# source.net
KiCad netlist of a schematic drawn in EasyEDA Pro
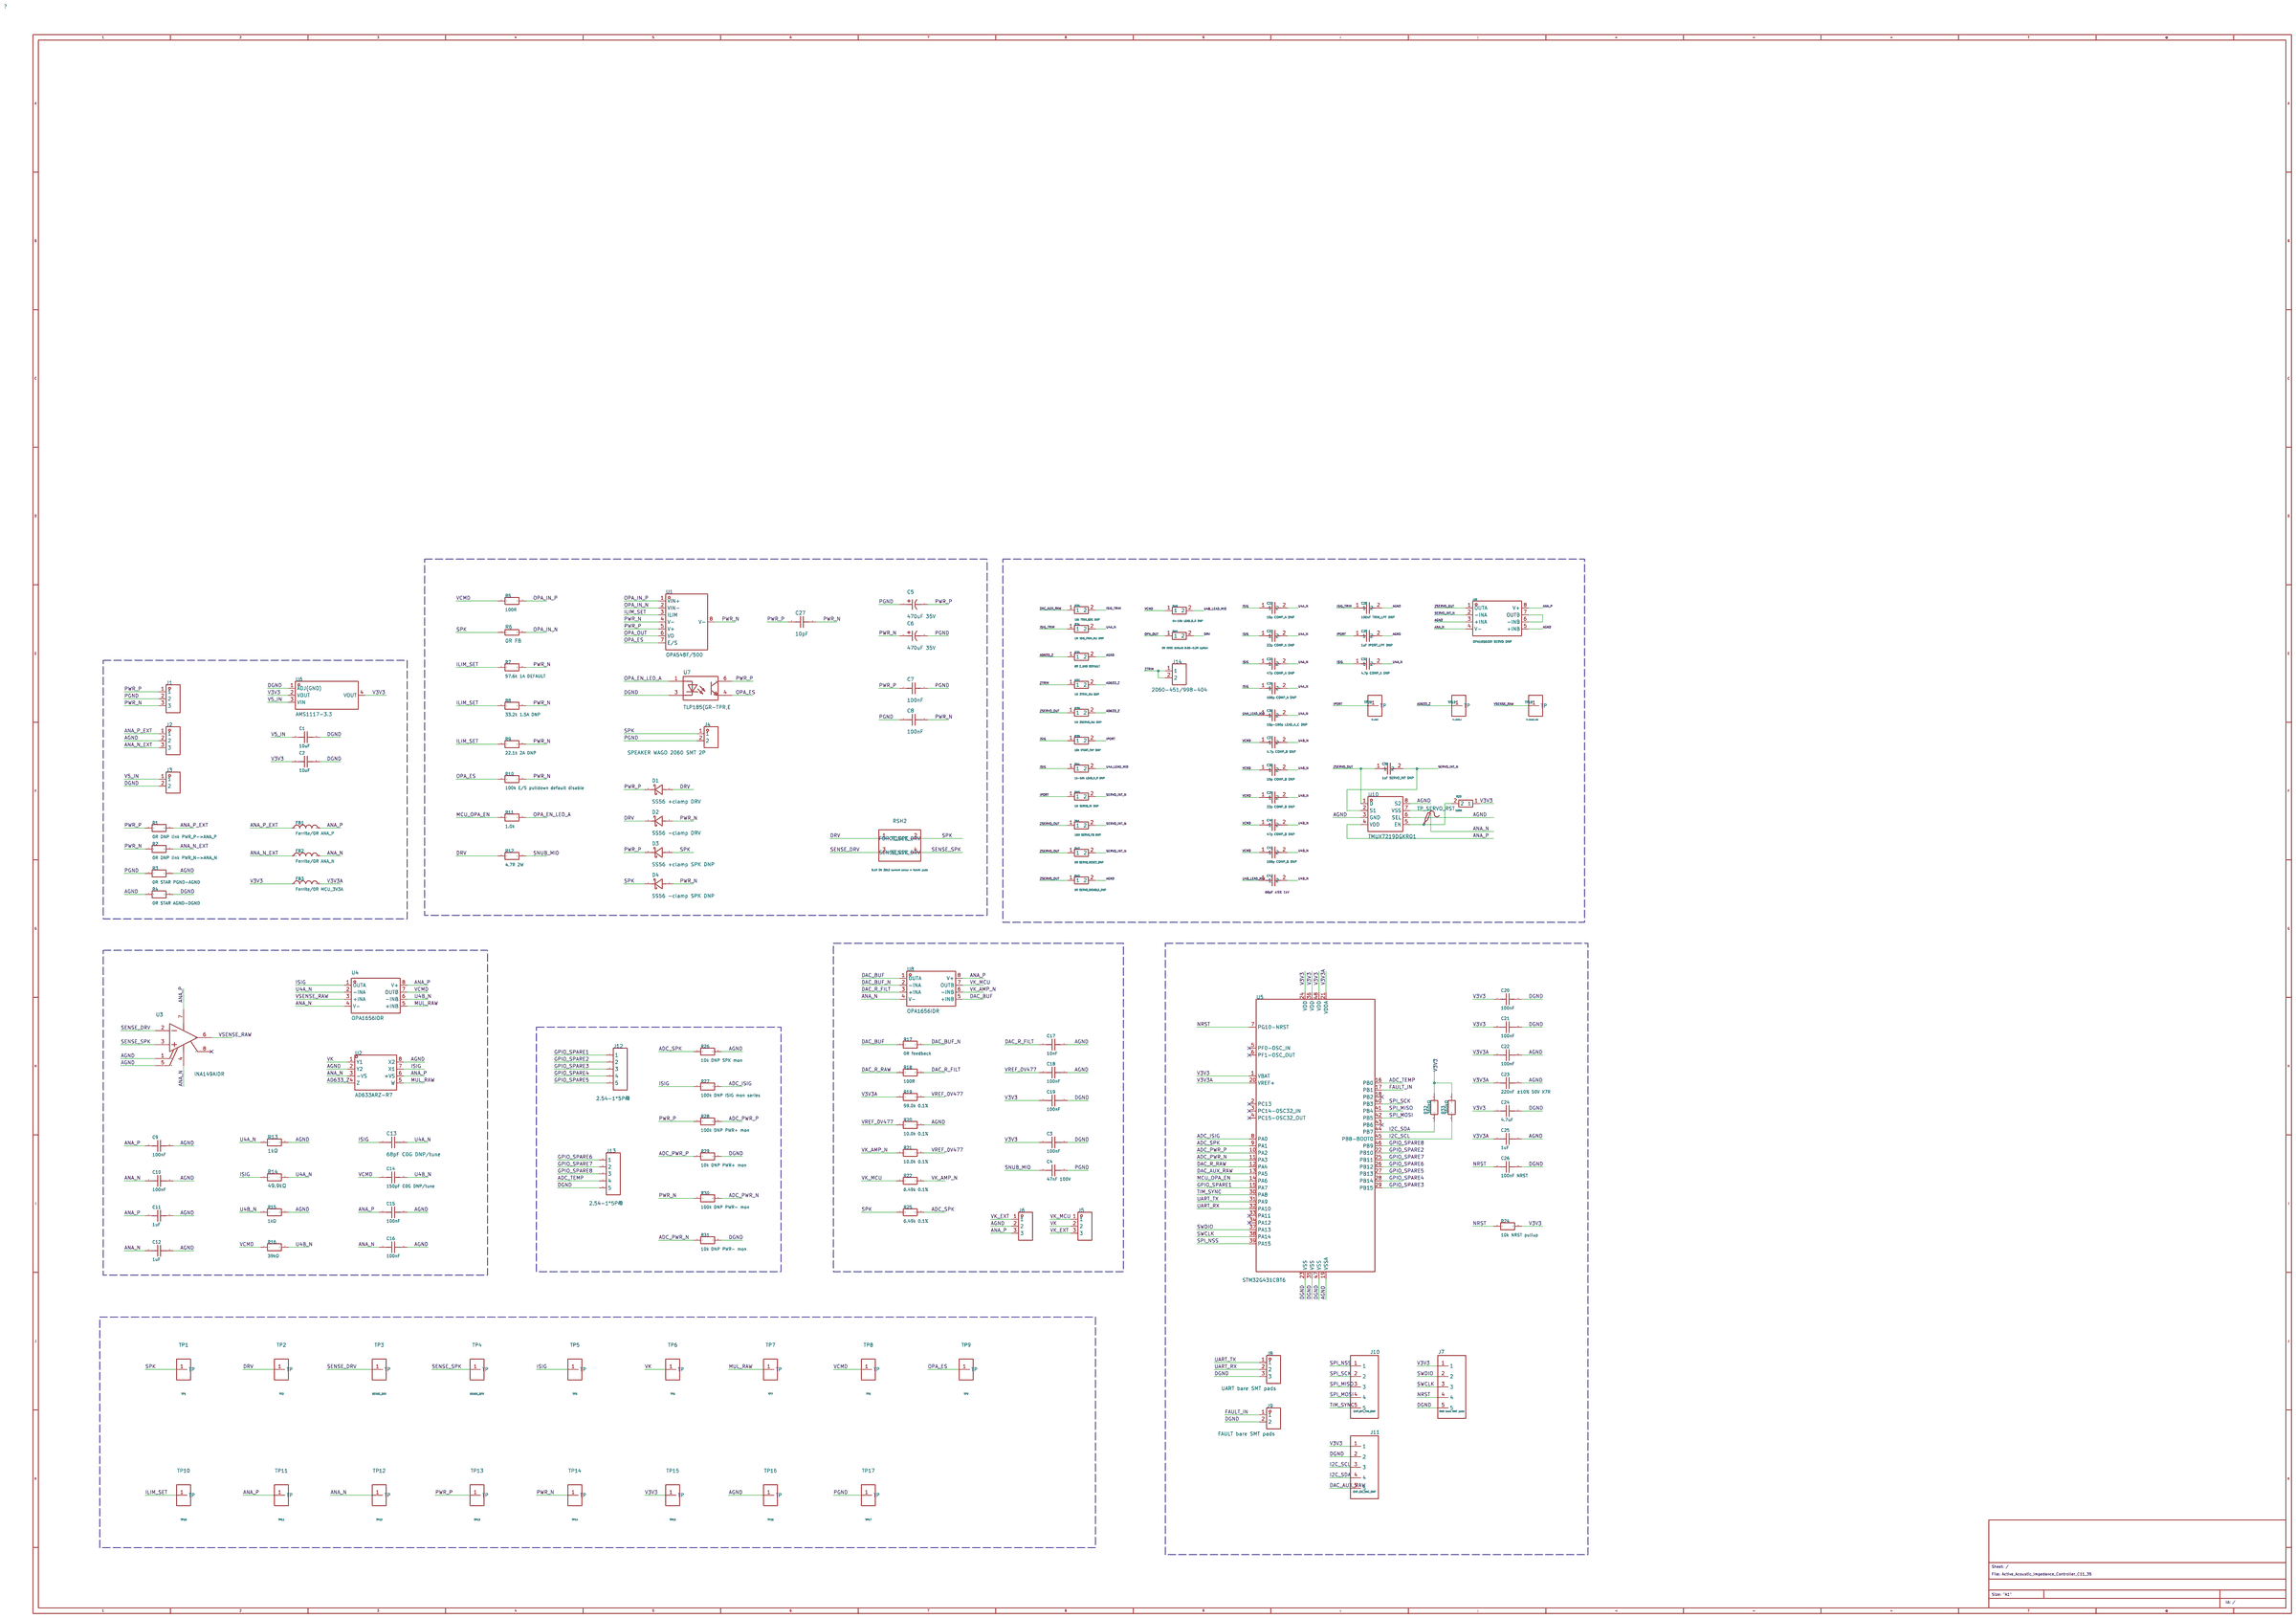
[diagram p0: schematic sheet]

(export (version "E")
  (design (tool "Eeschema 10.0.6"))
  (components
    (comp (ref "C1")
      (value "10uF")
      (footprint "easyedapro:C0805")
      (fields
        (field (name "Manufacturer Part") "AC0805KKX5R9BB225")
        (field (name "Manufacturer") "YAGEO(国巨)")
      )
      (libsource (lib "easyedapro") (part "AC0805KKX5R9BB225"))
    )
    (comp (ref "C2")
      (value "10uF")
      (footprint "easyedapro:C0805")
      (fields
        (field (name "Manufacturer Part") "AC0805KKX5R9BB225")
        (field (name "Manufacturer") "YAGEO(国巨)")
      )
      (libsource (lib "easyedapro") (part "AC0805KKX5R9BB225"))
    )
    (comp (ref "C3")
      (value "100nF")
      (footprint "easyedapro:C0805")
      (fields
        (field (name "Manufacturer Part") "CL21A106KAYNNNG")
        (field (name "Manufacturer") "SAMSUNG(三星)")
      )
      (libsource (lib "easyedapro") (part "CL21A106KAYNNNG"))
    )
    (comp (ref "C4")
      (value "47nF 100V")
      (footprint "easyedapro:C0805")
      (fields
        (field (name "Manufacturer Part") "CL21A106KAYNNNG")
        (field (name "Manufacturer") "SAMSUNG(三星)")
      )
      (libsource (lib "easyedapro") (part "CL21A106KAYNNNG"))
    )
    (comp (ref "C5")
      (value "470uF 35V")
      (footprint "easyedapro:CAP-SMD_BD10.0-L10.3-W10.3-LS11.3-FD")
      (fields
        (field (name "Manufacturer Part") "XT470UF35V90RV0080")
        (field (name "Manufacturer") "KNSCHA(科尼盛)")
      )
      (libsource (lib "easyedapro") (part "XT470UF35V90RV0080"))
    )
    (comp (ref "C6")
      (value "470uF 35V")
      (footprint "easyedapro:CAP-SMD_BD10.0-L10.3-W10.3-LS11.3-FD")
      (fields
        (field (name "Manufacturer Part") "XT470UF35V90RV0080")
        (field (name "Manufacturer") "KNSCHA(科尼盛)")
      )
      (libsource (lib "easyedapro") (part "XT470UF35V90RV0080"))
    )
    (comp (ref "C7")
      (value "100nF")
      (footprint "easyedapro:C0805")
      (fields
        (field (name "Manufacturer Part") "CC0805KRX7R9BB104")
        (field (name "Manufacturer") "YAGEO(国巨)")
      )
      (libsource (lib "easyedapro") (part "CC0805KRX7R9BB104"))
    )
    (comp (ref "C8")
      (value "100nF")
      (footprint "easyedapro:C0805")
      (fields
        (field (name "Manufacturer Part") "CC0805KRX7R9BB104")
        (field (name "Manufacturer") "YAGEO(国巨)")
      )
      (libsource (lib "easyedapro") (part "CC0805KRX7R9BB104"))
    )
    (comp (ref "C9")
      (value "100nF")
      (footprint "easyedapro:C0805")
      (fields
        (field (name "Manufacturer Part") "CSA0805X7R104K201MT")
        (field (name "Manufacturer") "HRE(芯声)")
      )
      (libsource (lib "easyedapro") (part "CSA0805X7R104K201MT"))
    )
    (comp (ref "C10")
      (value "100nF")
      (footprint "easyedapro:C0805")
      (fields
        (field (name "Manufacturer Part") "CSA0805X7R104K201MT")
        (field (name "Manufacturer") "HRE(芯声)")
      )
      (libsource (lib "easyedapro") (part "CSA0805X7R104K201MT"))
    )
    (comp (ref "C11")
      (value "1uF")
      (footprint "easyedapro:C0805")
      (fields (field (name "Manufacturer Part") "C0805Y5V250-105ZNE") (field (name "Manufacturer") "Venkel"))
      (libsource (lib "easyedapro") (part "C0805Y5V250-105ZNE"))
    )
    (comp (ref "C12")
      (value "1uF")
      (footprint "easyedapro:C0805")
      (fields (field (name "Manufacturer Part") "C0805Y5V250-105ZNE") (field (name "Manufacturer") "Venkel"))
      (libsource (lib "easyedapro") (part "C0805Y5V250-105ZNE"))
    )
    (comp (ref "C13")
      (value "68pF C0G DNP/tune")
      (footprint "easyedapro:C0805")
      (fields
        (field (name "Manufacturer Part") "FV21N680J102ECG")
        (field (name "Manufacturer") "PSA(信昌电陶)")
        (field (name "Tolerance") "±5%")
      )
      (libsource (lib "easyedapro") (part "FV21N680J102ECG"))
    )
    (comp (ref "C14")
      (value "150pF C0G DNP/tune")
      (footprint "easyedapro:C0805")
      (fields
        (field (name "Manufacturer Part") "CSA0805X7R104K201MT")
        (field (name "Manufacturer") "HRE(芯声)")
      )
      (libsource (lib "easyedapro") (part "CSA0805X7R104K201MT"))
    )
    (comp (ref "C15")
      (value "100nF")
      (footprint "easyedapro:C0805")
      (fields
        (field (name "Manufacturer Part") "CSA0805X7R104K201MT")
        (field (name "Manufacturer") "HRE(芯声)")
      )
      (libsource (lib "easyedapro") (part "CSA0805X7R104K201MT"))
    )
    (comp (ref "C16")
      (value "100nF")
      (footprint "easyedapro:C0805")
      (fields
        (field (name "Manufacturer Part") "CSA0805X7R104K201MT")
        (field (name "Manufacturer") "HRE(芯声)")
      )
      (libsource (lib "easyedapro") (part "CSA0805X7R104K201MT"))
    )
    (comp (ref "C17")
      (value "10nF")
      (footprint "easyedapro:C0805")
      (fields
        (field (name "Manufacturer Part") "CL21A106KAYNNNG")
        (field (name "Manufacturer") "SAMSUNG(三星)")
      )
      (libsource (lib "easyedapro") (part "CL21A106KAYNNNG"))
    )
    (comp (ref "C18")
      (value "100nF")
      (footprint "easyedapro:C0805")
      (fields
        (field (name "Manufacturer Part") "CL21A106KAYNNNG")
        (field (name "Manufacturer") "SAMSUNG(三星)")
      )
      (libsource (lib "easyedapro") (part "CL21A106KAYNNNG"))
    )
    (comp (ref "C19")
      (value "100nF")
      (footprint "easyedapro:C0805")
      (fields
        (field (name "Manufacturer Part") "CL21A106KAYNNNG")
        (field (name "Manufacturer") "SAMSUNG(三星)")
      )
      (libsource (lib "easyedapro") (part "CL21A106KAYNNNG"))
    )
    (comp (ref "C20")
      (value "100nF")
      (footprint "easyedapro:C0805")
      (fields
        (field (name "Manufacturer Part") "CL21B224KCQVPNE")
        (field (name "Manufacturer") "SAMSUNG(三星)")
      )
      (libsource (lib "easyedapro") (part "CL21B224KCQVPNE"))
    )
    (comp (ref "C21")
      (value "100nF")
      (footprint "easyedapro:C0805")
      (fields
        (field (name "Manufacturer Part") "CL21B224KCQVPNE")
        (field (name "Manufacturer") "SAMSUNG(三星)")
      )
      (libsource (lib "easyedapro") (part "CL21B224KCQVPNE"))
    )
    (comp (ref "C22")
      (value "100nF")
      (footprint "easyedapro:C0805")
      (fields
        (field (name "Manufacturer Part") "CL21B224KCQVPNE")
        (field (name "Manufacturer") "SAMSUNG(三星)")
      )
      (libsource (lib "easyedapro") (part "CL21B224KCQVPNE"))
    )
    (comp (ref "C23")
      (value "220nF ±10% 50V X7R")
      (footprint "easyedapro:C0805")
      (fields
        (field (name "Manufacturer Part") "CL21B224KCQVPNE")
        (field (name "Manufacturer") "SAMSUNG(三星)")
      )
      (libsource (lib "easyedapro") (part "CL21B224KCQVPNE"))
    )
    (comp (ref "C24")
      (value "4.7uF")
      (footprint "easyedapro:C0805")
      (fields
        (field (name "Manufacturer Part") "CL21B224KCQVPNE")
        (field (name "Manufacturer") "SAMSUNG(三星)")
      )
      (libsource (lib "easyedapro") (part "CL21B224KCQVPNE"))
    )
    (comp (ref "C25")
      (value "1uF")
      (footprint "easyedapro:C0805")
      (fields
        (field (name "Manufacturer Part") "CL21B224KCQVPNE")
        (field (name "Manufacturer") "SAMSUNG(三星)")
      )
      (libsource (lib "easyedapro") (part "CL21B224KCQVPNE"))
    )
    (comp (ref "C26")
      (value "100nF NRST")
      (footprint "easyedapro:C0805")
      (fields
        (field (name "Manufacturer Part") "CL21B224KCQVPNE")
        (field (name "Manufacturer") "SAMSUNG(三星)")
      )
      (libsource (lib "easyedapro") (part "CL21B224KCQVPNE"))
    )
    (comp (ref "C27")
      (value "10pF")
      (footprint "easyedapro:C0805")
      (fields (field (name "Manufacturer Part") "0805CG100J501NT") (field (name "Manufacturer") "FH(风华)"))
      (libsource (lib "easyedapro") (part "0805CG100J501NT"))
    )
    (comp (ref "C28")
      (value "100nF TRIM_LPF DNP")
      (fields (field (name "Manufacturer Part") "FV21N680J102ECG") (field (name "Manufacturer") "PSA(信昌电陶)"))
      (libsource (lib "easyedapro") (part "ProPrj_正弦电-easyedapro_FV21N680J102ECG"))
    )
    (comp (ref "C29")
      (value "1uF IPORT_LPF DNP")
      (fields (field (name "Manufacturer Part") "FV21N680J102ECG") (field (name "Manufacturer") "PSA(信昌电陶)"))
      (libsource (lib "easyedapro") (part "ProPrj_正弦电-easyedapro_FV21N680J102ECG"))
    )
    (comp (ref "C30")
      (value "1uF SERVO_INT DNP")
      (fields (field (name "Manufacturer Part") "FV21N680J102ECG") (field (name "Manufacturer") "PSA(信昌电陶)"))
      (libsource (lib "easyedapro") (part "ProPrj_正弦电-easyedapro_FV21N680J102ECG"))
    )
    (comp (ref "C31")
      (value "4.7p COMP_A DNP")
      (fields (field (name "Manufacturer Part") "FV21N680J102ECG") (field (name "Manufacturer") "PSA(信昌电陶)"))
      (libsource (lib "easyedapro") (part "ProPrj_正弦电-easyedapro_FV21N680J102ECG"))
    )
    (comp (ref "C32")
      (value "10p COMP_A DNP")
      (fields (field (name "Manufacturer Part") "FV21N680J102ECG") (field (name "Manufacturer") "PSA(信昌电陶)"))
      (libsource (lib "easyedapro") (part "ProPrj_正弦电-easyedapro_FV21N680J102ECG"))
    )
    (comp (ref "C33")
      (value "22p COMP_A DNP")
      (fields (field (name "Manufacturer Part") "FV21N680J102ECG") (field (name "Manufacturer") "PSA(信昌电陶)"))
      (libsource (lib "easyedapro") (part "ProPrj_正弦电-easyedapro_FV21N680J102ECG"))
    )
    (comp (ref "C34")
      (value "47p COMP_A DNP")
      (fields (field (name "Manufacturer Part") "FV21N680J102ECG") (field (name "Manufacturer") "PSA(信昌电陶)"))
      (libsource (lib "easyedapro") (part "ProPrj_正弦电-easyedapro_FV21N680J102ECG"))
    )
    (comp (ref "C35")
      (value "100p COMP_A DNP")
      (fields (field (name "Manufacturer Part") "FV21N680J102ECG") (field (name "Manufacturer") "PSA(信昌电陶)"))
      (libsource (lib "easyedapro") (part "ProPrj_正弦电-easyedapro_FV21N680J102ECG"))
    )
    (comp (ref "C36")
      (value "10p-100p LEAD_A_C DNP")
      (fields (field (name "Manufacturer Part") "FV21N680J102ECG") (field (name "Manufacturer") "PSA(信昌电陶)"))
      (libsource (lib "easyedapro") (part "ProPrj_正弦电-easyedapro_FV21N680J102ECG"))
    )
    (comp (ref "C37")
      (value "4.7p COMP_B DNP")
      (fields (field (name "Manufacturer Part") "FV21N680J102ECG") (field (name "Manufacturer") "PSA(信昌电陶)"))
      (libsource (lib "easyedapro") (part "ProPrj_正弦电-easyedapro_FV21N680J102ECG"))
    )
    (comp (ref "C38")
      (value "10p COMP_B DNP")
      (fields (field (name "Manufacturer Part") "FV21N680J102ECG") (field (name "Manufacturer") "PSA(信昌电陶)"))
      (libsource (lib "easyedapro") (part "ProPrj_正弦电-easyedapro_FV21N680J102ECG"))
    )
    (comp (ref "C39")
      (value "22p COMP_B DNP")
      (fields (field (name "Manufacturer Part") "FV21N680J102ECG") (field (name "Manufacturer") "PSA(信昌电陶)"))
      (libsource (lib "easyedapro") (part "ProPrj_正弦电-easyedapro_FV21N680J102ECG"))
    )
    (comp (ref "C40")
      (value "47p COMP_B DNP")
      (fields (field (name "Manufacturer Part") "FV21N680J102ECG") (field (name "Manufacturer") "PSA(信昌电陶)"))
      (libsource (lib "easyedapro") (part "ProPrj_正弦电-easyedapro_FV21N680J102ECG"))
    )
    (comp (ref "C41")
      (value "100p COMP_B DNP")
      (fields (field (name "Manufacturer Part") "FV21N680J102ECG") (field (name "Manufacturer") "PSA(信昌电陶)"))
      (libsource (lib "easyedapro") (part "ProPrj_正弦电-easyedapro_FV21N680J102ECG"))
    )
    (comp (ref "C42")
      (value "10p-100p LEAD_B_C DNP")
      (fields
        (field (name "Manufacturer Part") "FV21N680J102ECG")
        (field (name "Manufacturer") "PSA(信昌电陶)")
        (field (name "LCSC Part Name") "68pF ±5% 1kV")
      )
      (libsource (lib "easyedapro") (part "ProPrj_正弦电-easyedapro_FV21N680J102ECG"))
    )
    (comp (ref "D1")
      (value "SS56 +clamp DRV")
      (footprint "easyedapro:SMB_L4.3-W3.6-LS5.4-RD")
      (libsource (lib "easyedapro") (part "SS56_C9900018665"))
    )
    (comp (ref "D2")
      (value "SS56 -clamp DRV")
      (footprint "easyedapro:SMB_L4.3-W3.6-LS5.4-RD")
      (libsource (lib "easyedapro") (part "SS56_C9900018665"))
    )
    (comp (ref "D3")
      (value "SS56 +clamp SPK DNP")
      (footprint "easyedapro:SMB_L4.3-W3.6-LS5.4-RD")
      (libsource (lib "easyedapro") (part "SS56_C9900018665"))
    )
    (comp (ref "D4")
      (value "SS56 -clamp SPK DNP")
      (footprint "easyedapro:SMB_L4.3-W3.6-LS5.4-RD")
      (libsource (lib "easyedapro") (part "SS56_C9900018665"))
    )
    (comp (ref "FB1")
      (value "Ferrite/0R ANA_P")
      (footprint "easyedapro:L0805")
      (fields (field (name "Manufacturer") "MetalLions(美铼)"))
      (libsource (lib "easyedapro") (part "MLB2012F-151T"))
    )
    (comp (ref "FB2")
      (value "Ferrite/0R ANA_N")
      (footprint "easyedapro:L0805")
      (fields (field (name "Manufacturer") "MetalLions(美铼)"))
      (libsource (lib "easyedapro") (part "MLB2012F-151T"))
    )
    (comp (ref "FB3")
      (value "Ferrite/0R MCU_3V3A")
      (footprint "easyedapro:L0805")
      (fields (field (name "Manufacturer") "MetalLions(美铼)"))
      (libsource (lib "easyedapro") (part "MLB2012F-151T"))
    )
    (comp (ref "J1")
      (value "2060-453/998-404")
      (footprint "easyedapro:CONN-SMD_2060-453")
      (fields (field (name "Manufacturer") "WAGO(万可)"))
      (libsource (lib "easyedapro") (part "2060-453/998-404"))
    )
    (comp (ref "J2")
      (value "2060-453/998-404")
      (footprint "easyedapro:CONN-SMD_2060-453")
      (fields (field (name "Manufacturer") "WAGO(万可)"))
      (libsource (lib "easyedapro") (part "2060-453/998-404"))
    )
    (comp (ref "J3")
      (value "2060-452/998-404")
      (footprint "easyedapro:CONN-SMD_2060-452")
      (fields (field (name "Manufacturer") "WAGO(万可)"))
      (libsource (lib "easyedapro") (part "2060-452/998-404"))
    )
    (comp (ref "J4")
      (value "SPEAKER WAGO 2060 SMT 2P")
      (footprint "easyedapro:CONN-SMD_2060-452")
      (fields (field (name "Manufacturer") "WAGO(万可)"))
      (libsource (lib "easyedapro") (part "2060-452/998-404"))
    )
    (comp (ref "J5")
      (value "2060-453/998-404")
      (footprint "easyedapro:CONN-SMD_2060-453")
      (fields (field (name "Manufacturer") "WAGO(万可)"))
      (libsource (lib "easyedapro") (part "2060-453/998-404"))
    )
    (comp (ref "J6")
      (value "2060-453/998-404")
      (footprint "easyedapro:CONN-SMD_2060-453")
      (fields (field (name "Manufacturer") "WAGO(万可)"))
      (libsource (lib "easyedapro") (part "2060-453/998-404"))
    )
    (comp (ref "J7")
      (value "SWD bare SMT pads")
      (footprint "easyedapro:AAI_C11_35_LOCAL_Footprints:AAI_PinHeader_1x05_P2_54mm_Vertical")
      (libsource (lib "easyedapro") (part "AAI_CONN_01X05"))
    )
    (comp (ref "J8")
      (value "UART bare SMT pads")
      (footprint "easyedapro:CONN-SMD_2060-453")
      (fields (field (name "Manufacturer") "WAGO(万可)"))
      (libsource (lib "easyedapro") (part "2060-453/998-404"))
    )
    (comp (ref "J9")
      (value "FAULT bare SMT pads")
      (footprint "easyedapro:CONN-SMD_2060-452")
      (fields (field (name "Manufacturer Part") "2060-452/998-404") (field (name "Manufacturer") "WAGO(万可)"))
      (libsource (lib "easyedapro") (part "2060-452/998-404"))
    )
    (comp (ref "J10")
      (value "EXP_SPI_TIM_DNP")
      (footprint "easyedapro:AAI_C11_35_LOCAL_Footprints:AAI_PinHeader_1x05_P2_54mm_Vertical")
      (libsource (lib "easyedapro") (part "AAI_CONN_01X05"))
    )
    (comp (ref "J11")
      (value "EXP_I2C_DAC_DNP")
      (footprint "easyedapro:AAI_C11_35_LOCAL_Footprints:AAI_PinHeader_1x05_P2_54mm_Vertical")
      (libsource (lib "easyedapro") (part "AAI_CONN_01X05"))
    )
    (comp (ref "J12")
      (value "2.54-1*5P母")
      (footprint "easyedapro:HDR-TH_5P-P2.54-V-F")
      (fields (field (name "Manufacturer") "BOOMELE(博穆精密)"))
      (libsource (lib "easyedapro") (part "Header-Female-2.54_1x5"))
    )
    (comp (ref "J13")
      (value "2.54-1*5P母")
      (footprint "easyedapro:HDR-TH_5P-P2.54-V-F")
      (fields (field (name "Manufacturer") "BOOMELE(博穆精密)"))
      (libsource (lib "easyedapro") (part "Header-Female-2.54_1x5"))
    )
    (comp (ref "J14")
      (value "2060-451/998-404")
      (footprint "easyedapro:CONN-SMD_L12.7-W3.9_2060-451-998-404")
      (fields (field (name "Manufacturer") "WAGO(万可)"))
      (libsource (lib "easyedapro") (part "2060-451/998-404"))
    )
    (comp (ref "R1")
      (value "0R DNP link PWR_P->ANA_P")
      (footprint "easyedapro:R0805")
      (fields
        (field (name "Manufacturer Part") "MCU08050D1000BP100")
        (field (name "Manufacturer") "VISHAY(威世)")
      )
      (libsource (lib "easyedapro") (part "MCU08050D1000BP100"))
    )
    (comp (ref "R2")
      (value "0R DNP link PWR_N->ANA_N")
      (footprint "easyedapro:R0805")
      (fields
        (field (name "Manufacturer Part") "MCU08050D1000BP100")
        (field (name "Manufacturer") "VISHAY(威世)")
      )
      (libsource (lib "easyedapro") (part "MCU08050D1000BP100"))
    )
    (comp (ref "R3")
      (value "0R STAR PGND-AGND")
      (footprint "easyedapro:R0805")
      (fields
        (field (name "Manufacturer Part") "MCU08050D1000BP100")
        (field (name "Manufacturer") "VISHAY(威世)")
      )
      (libsource (lib "easyedapro") (part "MCU08050D1000BP100"))
    )
    (comp (ref "R4")
      (value "0R STAR AGND-DGND")
      (footprint "easyedapro:R0805")
      (fields
        (field (name "Manufacturer Part") "MCU08050D1000BP100")
        (field (name "Manufacturer") "VISHAY(威世)")
      )
      (libsource (lib "easyedapro") (part "MCU08050D1000BP100"))
    )
    (comp (ref "R5")
      (value "100R")
      (footprint "easyedapro:R0805")
      (fields
        (field (name "Manufacturer Part") "MCU08050D1000BP100")
        (field (name "Manufacturer") "VISHAY(威世)")
      )
      (libsource (lib "easyedapro") (part "MCU08050D1000BP100"))
    )
    (comp (ref "R6")
      (value "0R FB")
      (footprint "easyedapro:R0805")
      (fields
        (field (name "Manufacturer Part") "0805W8F0000T5E")
        (field (name "Manufacturer") "UNI-ROYAL(厚声)")
      )
      (libsource (lib "easyedapro") (part "0805W8F0000T5E"))
    )
    (comp (ref "R7")
      (value "57.6k 1A DEFAULT")
      (footprint "easyedapro:R0805")
      (fields
        (field (name "Manufacturer Part") "MCU08050D1000BP100")
        (field (name "Manufacturer") "VISHAY(威世)")
      )
      (libsource (lib "easyedapro") (part "MCU08050D1000BP100"))
    )
    (comp (ref "R8")
      (value "33.2k 1.5A DNP")
      (footprint "easyedapro:R0805")
      (fields
        (field (name "Manufacturer Part") "MCU08050D1000BP100")
        (field (name "Manufacturer") "VISHAY(威世)")
      )
      (libsource (lib "easyedapro") (part "MCU08050D1000BP100"))
    )
    (comp (ref "R9")
      (value "22.1k 2A DNP")
      (footprint "easyedapro:R0805")
      (fields
        (field (name "Manufacturer Part") "MCU08050D1000BP100")
        (field (name "Manufacturer") "VISHAY(威世)")
      )
      (libsource (lib "easyedapro") (part "MCU08050D1000BP100"))
    )
    (comp (ref "R10")
      (value "100k E/S pulldown default disable")
      (footprint "easyedapro:R0805")
      (fields
        (field (name "Manufacturer Part") "MCU08050D1000BP100")
        (field (name "Manufacturer") "VISHAY(威世)")
      )
      (libsource (lib "easyedapro") (part "MCU08050D1000BP100"))
    )
    (comp (ref "R11")
      (value "1.0k")
      (footprint "easyedapro:R0805")
      (fields
        (field (name "Manufacturer Part") "MCU08050D1000BP100")
        (field (name "Manufacturer") "VISHAY(威世)")
      )
      (libsource (lib "easyedapro") (part "MCU08050D1000BP100"))
    )
    (comp (ref "R12")
      (value "4.7R 2W")
      (footprint "easyedapro:RES-SMD_L6.4-W3.2-R2512")
      (fields (field (name "Manufacturer Part") "RE2512F3R002") (field (name "Manufacturer") "JIERR(捷而瑞)"))
      (libsource (lib "easyedapro") (part "RE2512F3R002"))
    )
    (comp (ref "R13")
      (value "1kΩ")
      (footprint "easyedapro:R0805")
      (fields (field (name "Manufacturer Part") "THE05G1001FT") (field (name "Manufacturer") "FH(风华)"))
      (libsource (lib "easyedapro") (part "THE05G1001FT"))
    )
    (comp (ref "R14")
      (value "49.9kΩ")
      (footprint "easyedapro:R0805")
      (fields (field (name "Manufacturer Part") "CR0805-FX-4992ELF") (field (name "Manufacturer") "BOURNS"))
      (libsource (lib "easyedapro") (part "CR0805-FX-4992ELF"))
    )
    (comp (ref "R15")
      (value "1kΩ")
      (footprint "easyedapro:R0805")
      (fields (field (name "Manufacturer Part") "CL0805FN1KPS") (field (name "Manufacturer") "昶龙科技"))
      (libsource (lib "easyedapro") (part "CL0805FN1KPS"))
    )
    (comp (ref "R16")
      (value "39kΩ")
      (footprint "easyedapro:R0805")
      (fields (field (name "Manufacturer Part") "CL0805FN1KPS") (field (name "Manufacturer") "昶龙科技"))
      (libsource (lib "easyedapro") (part "CL0805FN1KPS"))
    )
    (comp (ref "R17")
      (value "0R feedback")
      (footprint "easyedapro:R0805")
      (fields (field (name "Manufacturer Part") "CL0805JN1R6PS") (field (name "Manufacturer") "昶龙科技"))
      (libsource (lib "easyedapro") (part "CL0805JN1R6PS"))
    )
    (comp (ref "R18")
      (value "100R")
      (footprint "easyedapro:R0805")
      (fields (field (name "Manufacturer Part") "CL0805JN1R6PS") (field (name "Manufacturer") "昶龙科技"))
      (libsource (lib "easyedapro") (part "CL0805JN1R6PS"))
    )
    (comp (ref "R19")
      (value "59.0k 0.1%")
      (footprint "easyedapro:R0805")
      (fields (field (name "Manufacturer Part") "CL0805JN1R6PS") (field (name "Manufacturer") "昶龙科技"))
      (libsource (lib "easyedapro") (part "CL0805JN1R6PS"))
    )
    (comp (ref "R20")
      (value "10.0k 0.1%")
      (footprint "easyedapro:R0805")
      (fields (field (name "Manufacturer Part") "CL0805JN1R6PS") (field (name "Manufacturer") "昶龙科技"))
      (libsource (lib "easyedapro") (part "CL0805JN1R6PS"))
    )
    (comp (ref "R21")
      (value "10.0k 0.1%")
      (footprint "easyedapro:R0805")
      (fields (field (name "Manufacturer Part") "CL0805JN1R6PS") (field (name "Manufacturer") "昶龙科技"))
      (libsource (lib "easyedapro") (part "CL0805JN1R6PS"))
    )
    (comp (ref "R22")
      (value "6.49k 0.1%")
      (footprint "easyedapro:R0805")
      (fields (field (name "Manufacturer Part") "CL0805JN1R6PS") (field (name "Manufacturer") "昶龙科技"))
      (libsource (lib "easyedapro") (part "CL0805JN1R6PS"))
    )
    (comp (ref "R23")
      (value "100K")
      (fields
        (field (name "Manufacturer Part") "MCU08050D1000BP100")
        (field (name "Manufacturer") "VISHAY(威世)")
      )
      (libsource (lib "easyedapro") (part "ProPrj_正弦电-easyedapro_MCU08050D1000BP100"))
    )
    (comp (ref "R24")
      (value "10k NRST pullup")
      (footprint "easyedapro:R0805")
      (fields (field (name "Manufacturer Part") "CL0805FN2R4PS") (field (name "Manufacturer") "昶龙科技"))
      (libsource (lib "easyedapro") (part "CL0805FN2R4PS"))
    )
    (comp (ref "R25")
      (value "6.49k 0.1%")
      (footprint "easyedapro:R0805")
      (fields (field (name "Manufacturer Part") "CL0805JN1R6PS") (field (name "Manufacturer") "昶龙科技"))
      (libsource (lib "easyedapro") (part "CL0805JN1R6PS"))
    )
    (comp (ref "R26")
      (value "10k DNP SPK mon")
      (footprint "easyedapro:R0805")
      (fields (field (name "Manufacturer Part") "CL0805JN1R6PS") (field (name "Manufacturer") "昶龙科技"))
      (libsource (lib "easyedapro") (part "CL0805JN1R6PS"))
    )
    (comp (ref "R27")
      (value "100k DNP ISIG mon series")
      (footprint "easyedapro:R0805")
      (fields (field (name "Manufacturer Part") "CL0805JN1R6PS") (field (name "Manufacturer") "昶龙科技"))
      (libsource (lib "easyedapro") (part "CL0805JN1R6PS"))
    )
    (comp (ref "R28")
      (value "100k DNP PWR+ mon")
      (footprint "easyedapro:R0805")
      (fields (field (name "Manufacturer Part") "CL0805JN1R6PS") (field (name "Manufacturer") "昶龙科技"))
      (libsource (lib "easyedapro") (part "CL0805JN1R6PS"))
    )
    (comp (ref "R29")
      (value "10k DNP PWR+ mon")
      (footprint "easyedapro:R0805")
      (fields (field (name "Manufacturer Part") "CL0805JN1R6PS") (field (name "Manufacturer") "昶龙科技"))
      (libsource (lib "easyedapro") (part "CL0805JN1R6PS"))
    )
    (comp (ref "R30")
      (value "100k DNP PWR- mon")
      (footprint "easyedapro:R0805")
      (fields (field (name "Manufacturer Part") "CL0805JN1R6PS") (field (name "Manufacturer") "昶龙科技"))
      (libsource (lib "easyedapro") (part "CL0805JN1R6PS"))
    )
    (comp (ref "R31")
      (value "10k DNP PWR- mon")
      (footprint "easyedapro:R0805")
      (fields (field (name "Manufacturer Part") "CL0805JN1R6PS") (field (name "Manufacturer") "昶龙科技"))
      (libsource (lib "easyedapro") (part "CL0805JN1R6PS"))
    )
    (comp (ref "R32")
      (value "360kΩ")
      (footprint "easyedapro:R0805")
      (fields (field (name "Manufacturer Part") "CL0805FN360KPS") (field (name "Manufacturer") "昶龙科技"))
      (libsource (lib "easyedapro") (part "CL0805FN360KPS"))
    )
    (comp (ref "R33")
      (value "360kΩ")
      (footprint "easyedapro:R0805")
      (fields (field (name "Manufacturer Part") "CL0805FN360KPS") (field (name "Manufacturer") "昶龙科技"))
      (libsource (lib "easyedapro") (part "CL0805FN360KPS"))
    )
    (comp (ref "R34")
      (value "1M ISIG_TRIM_INJ DNP")
      (fields
        (field (name "Manufacturer Part") "MCU08050D1000BP100")
        (field (name "Manufacturer") "VISHAY(威世)")
      )
      (libsource (lib "easyedapro") (part "ProPrj_正弦电-easyedapro_MCU08050D1000BP100"))
    )
    (comp (ref "R35")
      (value "10k TRIM_SRC DNP")
      (fields
        (field (name "Manufacturer Part") "MCU08050D1000BP100")
        (field (name "Manufacturer") "VISHAY(威世)")
      )
      (libsource (lib "easyedapro") (part "ProPrj_正弦电-easyedapro_MCU08050D1000BP100"))
    )
    (comp (ref "R36")
      (value "0R Z_GND DEFAULT")
      (fields
        (field (name "Manufacturer Part") "MCU08050D1000BP100")
        (field (name "Manufacturer") "VISHAY(威世)")
      )
      (libsource (lib "easyedapro") (part "ProPrj_正弦电-easyedapro_MCU08050D1000BP100"))
    )
    (comp (ref "R37")
      (value "1M ZTRIM_INJ DNP")
      (fields
        (field (name "Manufacturer Part") "MCU08050D1000BP100")
        (field (name "Manufacturer") "VISHAY(威世)")
      )
      (libsource (lib "easyedapro") (part "ProPrj_正弦电-easyedapro_MCU08050D1000BP100"))
    )
    (comp (ref "R38")
      (value "1M ZSERVO_INJ DNP")
      (fields
        (field (name "Manufacturer Part") "MCU08050D1000BP100")
        (field (name "Manufacturer") "VISHAY(威世)")
      )
      (libsource (lib "easyedapro") (part "ProPrj_正弦电-easyedapro_MCU08050D1000BP100"))
    )
    (comp (ref "R39")
      (value "10k IPORT_TAP DNP")
      (fields
        (field (name "Manufacturer Part") "MCU08050D1000BP100")
        (field (name "Manufacturer") "VISHAY(威世)")
      )
      (libsource (lib "easyedapro") (part "ProPrj_正弦电-easyedapro_MCU08050D1000BP100"))
    )
    (comp (ref "R40")
      (value "1M SERVO_IN DNP")
      (fields
        (field (name "Manufacturer Part") "MCU08050D1000BP100")
        (field (name "Manufacturer") "VISHAY(威世)")
      )
      (libsource (lib "easyedapro") (part "ProPrj_正弦电-easyedapro_MCU08050D1000BP100"))
    )
    (comp (ref "R41")
      (value "10M SERVO_FB DNP")
      (fields
        (field (name "Manufacturer Part") "MCU08050D1000BP100")
        (field (name "Manufacturer") "VISHAY(威世)")
      )
      (libsource (lib "easyedapro") (part "ProPrj_正弦电-easyedapro_MCU08050D1000BP100"))
    )
    (comp (ref "R42")
      (value "0R SERVO_RESET_DNP")
      (fields
        (field (name "Manufacturer Part") "MCU08050D1000BP100")
        (field (name "Manufacturer") "VISHAY(威世)")
      )
      (libsource (lib "easyedapro") (part "ProPrj_正弦电-easyedapro_MCU08050D1000BP100"))
    )
    (comp (ref "R43")
      (value "0R SERVO_DISABLE_DNP")
      (fields
        (field (name "Manufacturer Part") "MCU08050D1000BP100")
        (field (name "Manufacturer") "VISHAY(威世)")
      )
      (libsource (lib "easyedapro") (part "ProPrj_正弦电-easyedapro_MCU08050D1000BP100"))
    )
    (comp (ref "R44")
      (value "1k-10k LEAD_A_R DNP")
      (fields
        (field (name "Manufacturer Part") "MCU08050D1000BP100")
        (field (name "Manufacturer") "VISHAY(威世)")
      )
      (libsource (lib "easyedapro") (part "ProPrj_正弦电-easyedapro_MCU08050D1000BP100"))
    )
    (comp (ref "R45")
      (value "1k-10k LEAD_B_R DNP")
      (fields
        (field (name "Manufacturer Part") "MCU08050D1000BP100")
        (field (name "Manufacturer") "VISHAY(威世)")
      )
      (libsource (lib "easyedapro") (part "ProPrj_正弦电-easyedapro_MCU08050D1000BP100"))
    )
    (comp (ref "R46")
      (value "0R RISO default 0.05-0.2R option")
      (fields
        (field (name "Manufacturer Part") "MCU08050D1000BP100")
        (field (name "Manufacturer") "VISHAY(威世)")
      )
      (libsource (lib "easyedapro") (part "ProPrj_正弦电-easyedapro_MCU08050D1000BP100"))
    )
    (comp (ref "RSH2")
      (value "0.1R 3W 2512 current sense + Kelvin pads")
      (footprint "easyedapro:AAI_C11_35_LOCAL_Footprints:AAI_SHUNT_4T_3920_Kelvin")
      (fields
        (field (name "Manufacturer") "Milliohm")
        (field (name "JLCPCB Part #") "C2903476")
        (field (name "MPN") "HoJLR2512-3W-100mR-1%")
      )
      (libsource (lib "easyedapro") (part "AAI_SHUNT_4T"))
    )
    (comp (ref "TP1")
      (value "TP1")
      (footprint "easyedapro:AAI_C11_35_LOCAL_Footprints:AAI_TestPoint_THTPad_D1_5mm_Drill0_7mm")
      (libsource (lib "easyedapro") (part "AAI_TESTPOINT"))
    )
    (comp (ref "TP2")
      (value "TP2")
      (footprint "easyedapro:AAI_C11_35_LOCAL_Footprints:AAI_TestPoint_THTPad_D1_5mm_Drill0_7mm")
      (libsource (lib "easyedapro") (part "AAI_TESTPOINT"))
    )
    (comp (ref "TP3")
      (value "SENSE_DRV")
      (footprint "easyedapro:AAI_C11_35_LOCAL_Footprints:AAI_TestPoint_THTPad_D1_5mm_Drill0_7mm")
      (libsource (lib "easyedapro") (part "AAI_TESTPOINT"))
    )
    (comp (ref "TP4")
      (value "SENSE_SPK")
      (footprint "easyedapro:AAI_C11_35_LOCAL_Footprints:AAI_TestPoint_THTPad_D1_5mm_Drill0_7mm")
      (libsource (lib "easyedapro") (part "AAI_TESTPOINT"))
    )
    (comp (ref "TP5")
      (value "TP5")
      (footprint "easyedapro:AAI_C11_35_LOCAL_Footprints:AAI_TestPoint_THTPad_D1_5mm_Drill0_7mm")
      (libsource (lib "easyedapro") (part "AAI_TESTPOINT"))
    )
    (comp (ref "TP6")
      (value "TP6")
      (footprint "easyedapro:AAI_C11_35_LOCAL_Footprints:AAI_TestPoint_THTPad_D1_5mm_Drill0_7mm")
      (libsource (lib "easyedapro") (part "AAI_TESTPOINT"))
    )
    (comp (ref "TP7")
      (value "TP7")
      (footprint "easyedapro:AAI_C11_35_LOCAL_Footprints:AAI_TestPoint_THTPad_D1_5mm_Drill0_7mm")
      (libsource (lib "easyedapro") (part "AAI_TESTPOINT"))
    )
    (comp (ref "TP8")
      (value "TP8")
      (footprint "easyedapro:AAI_C11_35_LOCAL_Footprints:AAI_TestPoint_THTPad_D1_5mm_Drill0_7mm")
      (libsource (lib "easyedapro") (part "AAI_TESTPOINT"))
    )
    (comp (ref "TP9")
      (value "TP9")
      (footprint "easyedapro:AAI_C11_35_LOCAL_Footprints:AAI_TestPoint_THTPad_D1_5mm_Drill0_7mm")
      (libsource (lib "easyedapro") (part "AAI_TESTPOINT"))
    )
    (comp (ref "TP10")
      (value "TP10")
      (footprint "easyedapro:AAI_C11_35_LOCAL_Footprints:AAI_TestPoint_THTPad_D1_5mm_Drill0_7mm")
      (libsource (lib "easyedapro") (part "AAI_TESTPOINT"))
    )
    (comp (ref "TP11")
      (value "TP11")
      (footprint "easyedapro:AAI_C11_35_LOCAL_Footprints:AAI_TestPoint_THTPad_D1_5mm_Drill0_7mm")
      (libsource (lib "easyedapro") (part "AAI_TESTPOINT"))
    )
    (comp (ref "TP12")
      (value "TP12")
      (footprint "easyedapro:AAI_C11_35_LOCAL_Footprints:AAI_TestPoint_THTPad_D1_5mm_Drill0_7mm")
      (libsource (lib "easyedapro") (part "AAI_TESTPOINT"))
    )
    (comp (ref "TP13")
      (value "TP13")
      (footprint "easyedapro:AAI_C11_35_LOCAL_Footprints:AAI_TestPoint_THTPad_D1_5mm_Drill0_7mm")
      (libsource (lib "easyedapro") (part "AAI_TESTPOINT"))
    )
    (comp (ref "TP14")
      (value "TP14")
      (footprint "easyedapro:AAI_C11_35_LOCAL_Footprints:AAI_TestPoint_THTPad_D1_5mm_Drill0_7mm")
      (libsource (lib "easyedapro") (part "AAI_TESTPOINT"))
    )
    (comp (ref "TP15")
      (value "TP15")
      (footprint "easyedapro:AAI_C11_35_LOCAL_Footprints:AAI_TestPoint_THTPad_D1_5mm_Drill0_7mm")
      (libsource (lib "easyedapro") (part "AAI_TESTPOINT"))
    )
    (comp (ref "TP16")
      (value "TP16")
      (footprint "easyedapro:AAI_C11_35_LOCAL_Footprints:AAI_TestPoint_THTPad_D1_5mm_Drill0_7mm")
      (libsource (lib "easyedapro") (part "AAI_TESTPOINT"))
    )
    (comp (ref "TP17")
      (value "TP17")
      (footprint "easyedapro:AAI_C11_35_LOCAL_Footprints:AAI_TestPoint_THTPad_D1_5mm_Drill0_7mm")
      (libsource (lib "easyedapro") (part "AAI_TESTPOINT"))
    )
    (comp (ref "TP18")
      (value "TP_VSENSE_RAW")
      (libsource (lib "easyedapro") (part "ProPrj_正弦电-easyedapro_AAI_TESTPOINT"))
    )
    (comp (ref "TP19")
      (value "TP_AD633_Z")
      (libsource (lib "easyedapro") (part "ProPrj_正弦电-easyedapro_AAI_TESTPOINT"))
    )
    (comp (ref "TP20")
      (value "TP_IPORT")
      (libsource (lib "easyedapro") (part "ProPrj_正弦电-easyedapro_AAI_TESTPOINT"))
    )
    (comp (ref "TP_SERVO_RST")
      (value "~")
      (footprint "easyedapro:Test-Point-0.5mm")
      (libsource (lib "easyedapro") (part "Test-Point"))
    )
    (comp (ref "U1")
      (value "OPA548F/500")
      (footprint "easyedapro:TO-263-7_L10.2-W10.4-P1.27-LS14.4-TL")
      (fields (field (name "Manufacturer") "TI(德州仪器)"))
      (libsource (lib "easyedapro") (part "OPA548F/500"))
    )
    (comp (ref "U2")
      (value "AD633ARZ-R7")
      (footprint "easyedapro:SOIC-8_L4.9-W3.9-P1.27-LS6.0-BL")
      (fields (field (name "Manufacturer") "ADI(亚德诺)"))
      (libsource (lib "easyedapro") (part "AD633ARZ-R7"))
    )
    (comp (ref "U3")
      (value "INA149AIDR")
      (footprint "easyedapro:SOIC-8_L4.9-W3.9-P1.27-LS6.0-BL")
      (fields (field (name "Manufacturer") "TI(德州仪器)"))
      (libsource (lib "easyedapro") (part "INA149AIDR"))
    )
    (comp (ref "U4")
      (value "OPA1656IDR")
      (footprint "easyedapro:SOIC-8_L4.9-W3.9-P1.27-LS6.0-BL")
      (fields (field (name "Manufacturer") "TI(德州仪器)"))
      (libsource (lib "easyedapro") (part "OPA1656IDR"))
    )
    (comp (ref "U5")
      (value "STM32G431CBT6")
      (footprint "easyedapro:LQFP-48_L7.0-W7.0-P0.50-LS9.0-BL")
      (fields (field (name "Manufacturer") "ST(意法半导体)"))
      (libsource (lib "easyedapro") (part "STM32G431CBT6"))
    )
    (comp (ref "U6")
      (value "AMS1117-3.3")
      (footprint "easyedapro:SOT-223-3_L6.5-W3.4-P2.30-LS7.0-BR")
      (fields (field (name "Manufacturer") "YONGYUTAI(永裕泰)"))
      (libsource (lib "easyedapro") (part "AMS1117-3.3_C2891839"))
    )
    (comp (ref "U7")
      (value "TLP185(GR-TPR,E")
      (footprint "easyedapro:SOP-6_4P-L3.7-W4.6-P2.54-LS7.0-BL")
      (fields (field (name "Manufacturer") "TOSHIBA(东芝)"))
      (libsource (lib "easyedapro") (part "TLP185(GR-TPR,E(T"))
    )
    (comp (ref "U8")
      (value "OPA1656IDR")
      (footprint "easyedapro:SOIC-8_L4.9-W3.9-P1.27-LS6.0-BL")
      (fields (field (name "Manufacturer") "TI(德州仪器)"))
      (libsource (lib "easyedapro") (part "OPA1656IDR"))
    )
    (comp (ref "U9")
      (value "OPA1656IDR SERVO DNP")
      (fields (field (name "Manufacturer Part") "OPA1656IDR") (field (name "Manufacturer") "TI(德州仪器)"))
      (libsource (lib "easyedapro") (part "ProPrj_正弦电-easyedapro_OPA1656IDR"))
    )
    (comp (ref "U10")
      (value "TMUX7219DGKRQ1")
      (footprint "easyedapro:VSSOP-8_L3.0-W3.0-P0.65-LS4.9-BL")
      (fields (field (name "Manufacturer") "TI(德州仪器)"))
      (libsource (lib "easyedapro") (part "TMUX7219DGKRQ1"))
    )
  )
  (nets
    (net (code "1") (name "/AD633_Z") (class "Default")
      (node (ref "R36") (pin "1") (pinfunction "1_1") (pintype "unspecified"))
      (node (ref "R37") (pin "2") (pinfunction "2_2") (pintype "unspecified"))
      (node (ref "R38") (pin "2") (pinfunction "2_2") (pintype "unspecified"))
      (node (ref "TP19") (pin "1") (pinfunction "TP_1") (pintype "unspecified"))
      (node (ref "U2") (pin "4") (pinfunction "Z_4") (pintype "unspecified"))
    )
    (net (code "2") (name "/ADC_ISIG") (class "Default")
      (node (ref "R27") (pin "2") (pinfunction "2_2") (pintype "unspecified"))
      (node (ref "U5") (pin "8") (pinfunction "PA0_8") (pintype "unspecified"))
    )
    (net (code "3") (name "/ADC_PWR_N") (class "Default")
      (node (ref "R30") (pin "2") (pinfunction "2_2") (pintype "unspecified"))
      (node (ref "R31") (pin "1") (pinfunction "1_1") (pintype "unspecified"))
      (node (ref "U5") (pin "11") (pinfunction "PA3_11") (pintype "unspecified"))
    )
    (net (code "4") (name "/ADC_PWR_P") (class "Default")
      (node (ref "R28") (pin "2") (pinfunction "2_2") (pintype "unspecified"))
      (node (ref "R29") (pin "1") (pinfunction "1_1") (pintype "unspecified"))
      (node (ref "U5") (pin "10") (pinfunction "PA2_10") (pintype "unspecified"))
    )
    (net (code "5") (name "/ADC_SPK") (class "Default")
      (node (ref "R25") (pin "2") (pinfunction "2_2") (pintype "unspecified"))
      (node (ref "R26") (pin "1") (pinfunction "1_1") (pintype "unspecified"))
      (node (ref "U5") (pin "9") (pinfunction "PA1_9") (pintype "unspecified"))
    )
    (net (code "6") (name "/ADC_TEMP") (class "Default")
      (node (ref "J13") (pin "4") (pinfunction "4_4") (pintype "input"))
      (node (ref "U5") (pin "16") (pinfunction "PB0_16") (pintype "unspecified"))
    )
    (net (code "7") (name "/AGND") (class "Default")
      (node (ref "C10") (pin "2") (pinfunction "2_2") (pintype "unspecified"))
      (node (ref "C11") (pin "2") (pinfunction "2_2") (pintype "unspecified"))
      (node (ref "C12") (pin "2") (pinfunction "2_2") (pintype "unspecified"))
      (node (ref "C15") (pin "2") (pinfunction "2_2") (pintype "unspecified"))
      (node (ref "C16") (pin "2") (pinfunction "2_2") (pintype "unspecified"))
      (node (ref "C17") (pin "2") (pinfunction "2_2") (pintype "unspecified"))
      (node (ref "C18") (pin "2") (pinfunction "2_2") (pintype "unspecified"))
      (node (ref "C22") (pin "2") (pinfunction "2_2") (pintype "unspecified"))
      (node (ref "C23") (pin "2") (pinfunction "2_2") (pintype "unspecified"))
      (node (ref "C25") (pin "2") (pinfunction "2_2") (pintype "unspecified"))
      (node (ref "C28") (pin "2") (pinfunction "2_2") (pintype "unspecified"))
      (node (ref "C29") (pin "2") (pinfunction "2_2") (pintype "unspecified"))
      (node (ref "C9") (pin "2") (pinfunction "2_2") (pintype "unspecified"))
      (node (ref "J2") (pin "2") (pinfunction "2_2") (pintype "unspecified"))
      (node (ref "J6") (pin "2") (pinfunction "2_2") (pintype "unspecified"))
      (node (ref "R13") (pin "2") (pinfunction "2_2") (pintype "unspecified"))
      (node (ref "R15") (pin "2") (pinfunction "2_2") (pintype "unspecified"))
      (node (ref "R20") (pin "2") (pinfunction "2_2") (pintype "unspecified"))
      (node (ref "R26") (pin "2") (pinfunction "2_2") (pintype "unspecified"))
      (node (ref "R3") (pin "2") (pinfunction "2_2") (pintype "unspecified"))
      (node (ref "R36") (pin "2") (pinfunction "2_2") (pintype "unspecified"))
      (node (ref "R4") (pin "1") (pinfunction "1_1") (pintype "unspecified"))
      (node (ref "R43") (pin "2") (pinfunction "2_2") (pintype "unspecified"))
      (node (ref "TP16") (pin "1") (pinfunction "TP_1") (pintype "unspecified"))
      (node (ref "U10") (pin "3") (pinfunction "GND_3") (pintype "unspecified"))
      (node (ref "U10") (pin "6") (pinfunction "SEL_6") (pintype "unspecified"))
      (node (ref "U10") (pin "8") (pinfunction "S2_8") (pintype "unspecified"))
      (node (ref "U2") (pin "2") (pinfunction "Y2_2") (pintype "unspecified"))
      (node (ref "U2") (pin "8") (pinfunction "X2_8") (pintype "unspecified"))
      (node (ref "U3") (pin "1") (pinfunction "REFB_1") (pintype "unspecified"))
      (node (ref "U3") (pin "5") (pinfunction "REFA_5") (pintype "unspecified"))
      (node (ref "U5") (pin "19") (pinfunction "VSSA_19") (pintype "unspecified"))
      (node (ref "U9") (pin "3") (pinfunction "+INA_3") (pintype "unspecified"))
      (node (ref "U9") (pin "5") (pinfunction "+INB_5") (pintype "unspecified"))
    )
    (net (code "8") (name "/ANA_N") (class "Default")
      (node (ref "C10") (pin "1") (pinfunction "1_1") (pintype "unspecified"))
      (node (ref "C12") (pin "1") (pinfunction "1_1") (pintype "unspecified"))
      (node (ref "C16") (pin "1") (pinfunction "1_1") (pintype "unspecified"))
      (node (ref "FB2") (pin "2") (pinfunction "2_2") (pintype "unspecified"))
      (node (ref "TP12") (pin "1") (pinfunction "TP_1") (pintype "unspecified"))
      (node (ref "U10") (pin "7") (pinfunction "VSS_7") (pintype "unspecified"))
      (node (ref "U2") (pin "3") (pinfunction "-VS_3") (pintype "unspecified"))
      (node (ref "U3") (pin "4") (pinfunction "V-_4") (pintype "unspecified"))
      (node (ref "U4") (pin "4") (pinfunction "V-_4") (pintype "unspecified"))
      (node (ref "U8") (pin "4") (pinfunction "V-_4") (pintype "unspecified"))
      (node (ref "U9") (pin "4") (pinfunction "V-_4") (pintype "unspecified"))
    )
    (net (code "9") (name "/ANA_N_EXT") (class "Default")
      (node (ref "FB2") (pin "1") (pinfunction "1_1") (pintype "unspecified"))
      (node (ref "J2") (pin "3") (pinfunction "3_3") (pintype "unspecified"))
      (node (ref "R2") (pin "2") (pinfunction "2_2") (pintype "unspecified"))
    )
    (net (code "10") (name "/ANA_P") (class "Default")
      (node (ref "C11") (pin "1") (pinfunction "1_1") (pintype "unspecified"))
      (node (ref "C15") (pin "1") (pinfunction "1_1") (pintype "unspecified"))
      (node (ref "C9") (pin "1") (pinfunction "1_1") (pintype "unspecified"))
      (node (ref "FB1") (pin "2") (pinfunction "2_2") (pintype "unspecified"))
      (node (ref "J6") (pin "3") (pinfunction "3_3") (pintype "unspecified"))
      (node (ref "TP11") (pin "1") (pinfunction "TP_1") (pintype "unspecified"))
      (node (ref "U10") (pin "4") (pinfunction "VDD_4") (pintype "unspecified"))
      (node (ref "U2") (pin "6") (pinfunction "+VS_6") (pintype "unspecified"))
      (node (ref "U3") (pin "7") (pinfunction "V+_7") (pintype "unspecified"))
      (node (ref "U4") (pin "8") (pinfunction "V+_8") (pintype "unspecified"))
      (node (ref "U8") (pin "8") (pinfunction "V+_8") (pintype "unspecified"))
      (node (ref "U9") (pin "8") (pinfunction "V+_8") (pintype "unspecified"))
    )
    (net (code "11") (name "/ANA_P_EXT") (class "Default")
      (node (ref "FB1") (pin "1") (pinfunction "1_1") (pintype "unspecified"))
      (node (ref "J2") (pin "1") (pinfunction "1_1") (pintype "unspecified"))
      (node (ref "R1") (pin "2") (pinfunction "2_2") (pintype "unspecified"))
    )
    (net (code "12") (name "/DAC_AUX_RAW") (class "Default")
      (node (ref "J11") (pin "5") (pinfunction "5_5") (pintype "unspecified"))
      (node (ref "R35") (pin "1") (pinfunction "1_1") (pintype "unspecified"))
      (node (ref "U5") (pin "13") (pinfunction "PA5_13") (pintype "unspecified"))
    )
    (net (code "13") (name "/DAC_BUF") (class "Default")
      (node (ref "R17") (pin "1") (pinfunction "1_1") (pintype "unspecified"))
      (node (ref "U8") (pin "1") (pinfunction "OUTA_1") (pintype "unspecified"))
      (node (ref "U8") (pin "5") (pinfunction "+INB_5") (pintype "unspecified"))
    )
    (net (code "14") (name "/DAC_BUF_N") (class "Default")
      (node (ref "R17") (pin "2") (pinfunction "2_2") (pintype "unspecified"))
      (node (ref "U8") (pin "2") (pinfunction "-INA_2") (pintype "unspecified"))
    )
    (net (code "15") (name "/DAC_R_FILT") (class "Default")
      (node (ref "C17") (pin "1") (pinfunction "1_1") (pintype "unspecified"))
      (node (ref "R18") (pin "2") (pinfunction "2_2") (pintype "unspecified"))
      (node (ref "U8") (pin "3") (pinfunction "+INA_3") (pintype "unspecified"))
    )
    (net (code "16") (name "/DAC_R_RAW") (class "Default")
      (node (ref "R18") (pin "1") (pinfunction "1_1") (pintype "unspecified"))
      (node (ref "U5") (pin "12") (pinfunction "PA4_12") (pintype "unspecified"))
    )
    (net (code "17") (name "/DGND") (class "Default")
      (node (ref "C1") (pin "2") (pinfunction "2_2") (pintype "unspecified"))
      (node (ref "C19") (pin "2") (pinfunction "2_2") (pintype "unspecified"))
      (node (ref "C2") (pin "2") (pinfunction "2_2") (pintype "unspecified"))
      (node (ref "C20") (pin "2") (pinfunction "2_2") (pintype "unspecified"))
      (node (ref "C21") (pin "2") (pinfunction "2_2") (pintype "unspecified"))
      (node (ref "C24") (pin "2") (pinfunction "2_2") (pintype "unspecified"))
      (node (ref "C26") (pin "2") (pinfunction "2_2") (pintype "unspecified"))
      (node (ref "C3") (pin "2") (pinfunction "2_2") (pintype "unspecified"))
      (node (ref "J11") (pin "2") (pinfunction "2_2") (pintype "unspecified"))
      (node (ref "J13") (pin "5") (pinfunction "5_5") (pintype "input"))
      (node (ref "J3") (pin "2") (pinfunction "2_2") (pintype "unspecified"))
      (node (ref "J7") (pin "5") (pinfunction "5_5") (pintype "unspecified"))
      (node (ref "J8") (pin "3") (pinfunction "3_3") (pintype "unspecified"))
      (node (ref "J9") (pin "2") (pinfunction "2_2") (pintype "unspecified"))
      (node (ref "R29") (pin "2") (pinfunction "2_2") (pintype "unspecified"))
      (node (ref "R31") (pin "2") (pinfunction "2_2") (pintype "unspecified"))
      (node (ref "R4") (pin "2") (pinfunction "2_2") (pintype "unspecified"))
      (node (ref "U5") (pin "23") (pinfunction "VSS_23") (pintype "unspecified"))
      (node (ref "U5") (pin "35") (pinfunction "VSS_35") (pintype "unspecified"))
      (node (ref "U5") (pin "47") (pinfunction "VSS_47") (pintype "unspecified"))
      (node (ref "U6") (pin "1") (pinfunction "ADJ(GND)_1") (pintype "unspecified"))
      (node (ref "U7") (pin "3") (pinfunction "CAT_3") (pintype "unspecified"))
    )
    (net (code "18") (name "/DRV") (class "Default")
      (node (ref "D1") (pin "2") (pinfunction "A_2") (pintype "unspecified"))
      (node (ref "D2") (pin "1") (pinfunction "K_1") (pintype "unspecified"))
      (node (ref "R12") (pin "1") (pinfunction "1_1") (pintype "unspecified"))
      (node (ref "R46") (pin "2") (pinfunction "2_2") (pintype "unspecified"))
      (node (ref "RSH2") (pin "1") (pinfunction "FORCE_DRV_1") (pintype "unspecified"))
      (node (ref "TP2") (pin "1") (pinfunction "TP_1") (pintype "unspecified"))
    )
    (net (code "19") (name "/FAULT_IN") (class "Default")
      (node (ref "J9") (pin "1") (pinfunction "1_1") (pintype "unspecified"))
      (node (ref "U5") (pin "17") (pinfunction "PB1_17") (pintype "unspecified"))
    )
    (net (code "20") (name "/GPIO_SPARE1") (class "Default")
      (node (ref "J12") (pin "1") (pinfunction "1_1") (pintype "input"))
      (node (ref "U5") (pin "15") (pinfunction "PA7_15") (pintype "unspecified"))
    )
    (net (code "21") (name "/GPIO_SPARE2") (class "Default")
      (node (ref "J12") (pin "2") (pinfunction "2_2") (pintype "input"))
      (node (ref "U5") (pin "22") (pinfunction "PB10_22") (pintype "unspecified"))
    )
    (net (code "22") (name "/GPIO_SPARE3") (class "Default")
      (node (ref "J12") (pin "3") (pinfunction "3_3") (pintype "input"))
      (node (ref "U5") (pin "29") (pinfunction "PB15_29") (pintype "unspecified"))
    )
    (net (code "23") (name "/GPIO_SPARE4") (class "Default")
      (node (ref "J12") (pin "4") (pinfunction "4_4") (pintype "input"))
      (node (ref "U5") (pin "28") (pinfunction "PB14_28") (pintype "unspecified"))
    )
    (net (code "24") (name "/GPIO_SPARE5") (class "Default")
      (node (ref "J12") (pin "5") (pinfunction "5_5") (pintype "input"))
      (node (ref "U5") (pin "27") (pinfunction "PB13_27") (pintype "unspecified"))
    )
    (net (code "25") (name "/GPIO_SPARE6") (class "Default")
      (node (ref "J13") (pin "1") (pinfunction "1_1") (pintype "input"))
      (node (ref "U5") (pin "26") (pinfunction "PB12_26") (pintype "unspecified"))
    )
    (net (code "26") (name "/GPIO_SPARE7") (class "Default")
      (node (ref "J13") (pin "2") (pinfunction "2_2") (pintype "input"))
      (node (ref "U5") (pin "25") (pinfunction "PB11_25") (pintype "unspecified"))
    )
    (net (code "27") (name "/GPIO_SPARE8") (class "Default")
      (node (ref "J13") (pin "3") (pinfunction "3_3") (pintype "input"))
      (node (ref "U5") (pin "46") (pinfunction "PB9_46") (pintype "unspecified"))
    )
    (net (code "28") (name "/I2C_SCL") (class "Default")
      (node (ref "J11") (pin "3") (pinfunction "3_3") (pintype "unspecified"))
      (node (ref "R33") (pin "1") (pinfunction "1_1") (pintype "unspecified"))
      (node (ref "U5") (pin "45") (pinfunction "PB8-BOOT0_45") (pintype "unspecified"))
    )
    (net (code "29") (name "/I2C_SDA") (class "Default")
      (node (ref "J11") (pin "4") (pinfunction "4_4") (pintype "unspecified"))
      (node (ref "R32") (pin "1") (pinfunction "1_1") (pintype "unspecified"))
      (node (ref "U5") (pin "44") (pinfunction "PB7_44") (pintype "unspecified"))
    )
    (net (code "30") (name "/ILIM_SET") (class "Default")
      (node (ref "R7") (pin "1") (pinfunction "1_1") (pintype "unspecified"))
      (node (ref "R8") (pin "1") (pinfunction "1_1") (pintype "unspecified"))
      (node (ref "R9") (pin "1") (pinfunction "1_1") (pintype "unspecified"))
      (node (ref "TP10") (pin "1") (pinfunction "TP_1") (pintype "unspecified"))
      (node (ref "U1") (pin "3") (pinfunction "ILIM_3") (pintype "unspecified"))
    )
    (net (code "31") (name "/IPORT") (class "Default")
      (node (ref "C29") (pin "1") (pinfunction "1_1") (pintype "unspecified"))
      (node (ref "R39") (pin "2") (pinfunction "2_2") (pintype "unspecified"))
      (node (ref "R40") (pin "1") (pinfunction "1_1") (pintype "unspecified"))
      (node (ref "TP20") (pin "1") (pinfunction "TP_1") (pintype "unspecified"))
    )
    (net (code "32") (name "/ISIG") (class "Default")
      (node (ref "C13") (pin "1") (pinfunction "1_1") (pintype "unspecified"))
      (node (ref "C31") (pin "1") (pinfunction "1_1") (pintype "unspecified"))
      (node (ref "C32") (pin "1") (pinfunction "1_1") (pintype "unspecified"))
      (node (ref "C33") (pin "1") (pinfunction "1_1") (pintype "unspecified"))
      (node (ref "C34") (pin "1") (pinfunction "1_1") (pintype "unspecified"))
      (node (ref "C35") (pin "1") (pinfunction "1_1") (pintype "unspecified"))
      (node (ref "R14") (pin "1") (pinfunction "1_1") (pintype "unspecified"))
      (node (ref "R27") (pin "1") (pinfunction "1_1") (pintype "unspecified"))
      (node (ref "R39") (pin "1") (pinfunction "1_1") (pintype "unspecified"))
      (node (ref "R44") (pin "1") (pinfunction "1_1") (pintype "unspecified"))
      (node (ref "TP5") (pin "1") (pinfunction "TP_1") (pintype "unspecified"))
      (node (ref "U2") (pin "7") (pinfunction "X1_7") (pintype "unspecified"))
      (node (ref "U4") (pin "1") (pinfunction "OUTA_1") (pintype "unspecified"))
    )
    (net (code "33") (name "/ISIG_TRIM") (class "Default")
      (node (ref "C28") (pin "1") (pinfunction "1_1") (pintype "unspecified"))
      (node (ref "R34") (pin "1") (pinfunction "1_1") (pintype "unspecified"))
      (node (ref "R35") (pin "2") (pinfunction "2_2") (pintype "unspecified"))
    )
    (net (code "34") (name "/MCU_OPA_EN") (class "Default")
      (node (ref "R11") (pin "1") (pinfunction "1_1") (pintype "unspecified"))
      (node (ref "U5") (pin "14") (pinfunction "PA6_14") (pintype "unspecified"))
    )
    (net (code "35") (name "/MUL_RAW") (class "Default")
      (node (ref "TP7") (pin "1") (pinfunction "TP_1") (pintype "unspecified"))
      (node (ref "U2") (pin "5") (pinfunction "W_5") (pintype "unspecified"))
      (node (ref "U4") (pin "5") (pinfunction "+INB_5") (pintype "unspecified"))
    )
    (net (code "36") (name "/NRST") (class "Default")
      (node (ref "C26") (pin "1") (pinfunction "1_1") (pintype "unspecified"))
      (node (ref "J7") (pin "4") (pinfunction "4_4") (pintype "unspecified"))
      (node (ref "R24") (pin "1") (pinfunction "1_1") (pintype "unspecified"))
      (node (ref "U5") (pin "7") (pinfunction "PG10-NRST_7") (pintype "unspecified"))
    )
    (net (code "37") (name "/OPA_EN_LED_A") (class "Default")
      (node (ref "R11") (pin "2") (pinfunction "2_2") (pintype "unspecified"))
      (node (ref "U7") (pin "1") (pinfunction "AN_1") (pintype "unspecified"))
    )
    (net (code "38") (name "/OPA_ES") (class "Default")
      (node (ref "R10") (pin "1") (pinfunction "1_1") (pintype "unspecified"))
      (node (ref "TP9") (pin "1") (pinfunction "TP_1") (pintype "unspecified"))
      (node (ref "U1") (pin "7") (pinfunction "E/S_7") (pintype "unspecified"))
      (node (ref "U7") (pin "4") (pinfunction "EMI_4") (pintype "unspecified"))
    )
    (net (code "39") (name "/OPA_IN_N") (class "Default")
      (node (ref "R6") (pin "2") (pinfunction "2_2") (pintype "input"))
      (node (ref "U1") (pin "2") (pinfunction "VIN-_2") (pintype "unspecified"))
    )
    (net (code "40") (name "/OPA_IN_P") (class "Default")
      (node (ref "R5") (pin "2") (pinfunction "2_2") (pintype "unspecified"))
      (node (ref "U1") (pin "1") (pinfunction "VIN+_1") (pintype "unspecified"))
    )
    (net (code "41") (name "/OPA_OUT") (class "Default")
      (node (ref "R46") (pin "1") (pinfunction "1_1") (pintype "unspecified"))
      (node (ref "U1") (pin "6") (pinfunction "VO_6") (pintype "unspecified"))
    )
    (net (code "42") (name "/PGND") (class "Default")
      (node (ref "C4") (pin "2") (pinfunction "2_2") (pintype "unspecified"))
      (node (ref "C5") (pin "1") (pinfunction "1_1") (pintype "input"))
      (node (ref "C6") (pin "2") (pinfunction "2_2") (pintype "input"))
      (node (ref "C7") (pin "2") (pinfunction "2_2") (pintype "unspecified"))
      (node (ref "C8") (pin "1") (pinfunction "1_1") (pintype "unspecified"))
      (node (ref "J1") (pin "2") (pinfunction "2_2") (pintype "unspecified"))
      (node (ref "J4") (pin "2") (pinfunction "2_2") (pintype "unspecified"))
      (node (ref "R3") (pin "1") (pinfunction "1_1") (pintype "unspecified"))
      (node (ref "TP17") (pin "1") (pinfunction "TP_1") (pintype "unspecified"))
    )
    (net (code "43") (name "/PWR_N") (class "Default")
      (node (ref "C27") (pin "2") (pinfunction "2_2") (pintype "unspecified"))
      (node (ref "C6") (pin "1") (pinfunction "1_1") (pintype "input"))
      (node (ref "C8") (pin "2") (pinfunction "2_2") (pintype "unspecified"))
      (node (ref "D2") (pin "2") (pinfunction "A_2") (pintype "unspecified"))
      (node (ref "D4") (pin "2") (pinfunction "A_2") (pintype "unspecified"))
      (node (ref "J1") (pin "3") (pinfunction "3_3") (pintype "unspecified"))
      (node (ref "R10") (pin "2") (pinfunction "2_2") (pintype "unspecified"))
      (node (ref "R2") (pin "1") (pinfunction "1_1") (pintype "unspecified"))
      (node (ref "R30") (pin "1") (pinfunction "1_1") (pintype "unspecified"))
      (node (ref "R7") (pin "2") (pinfunction "2_2") (pintype "unspecified"))
      (node (ref "R8") (pin "2") (pinfunction "2_2") (pintype "unspecified"))
      (node (ref "R9") (pin "2") (pinfunction "2_2") (pintype "unspecified"))
      (node (ref "TP14") (pin "1") (pinfunction "TP_1") (pintype "unspecified"))
      (node (ref "U1") (pin "4") (pinfunction "V-_4") (pintype "unspecified"))
      (node (ref "U1") (pin "8") (pinfunction "V-_8") (pintype "unspecified"))
    )
    (net (code "44") (name "/PWR_P") (class "Default")
      (node (ref "C27") (pin "1") (pinfunction "1_1") (pintype "unspecified"))
      (node (ref "C5") (pin "2") (pinfunction "2_2") (pintype "input"))
      (node (ref "C7") (pin "1") (pinfunction "1_1") (pintype "unspecified"))
      (node (ref "D1") (pin "1") (pinfunction "K_1") (pintype "unspecified"))
      (node (ref "D3") (pin "1") (pinfunction "K_1") (pintype "unspecified"))
      (node (ref "J1") (pin "1") (pinfunction "1_1") (pintype "unspecified"))
      (node (ref "R1") (pin "1") (pinfunction "1_1") (pintype "unspecified"))
      (node (ref "R28") (pin "1") (pinfunction "1_1") (pintype "unspecified"))
      (node (ref "TP13") (pin "1") (pinfunction "TP_1") (pintype "unspecified"))
      (node (ref "U1") (pin "5") (pinfunction "V+_5") (pintype "unspecified"))
      (node (ref "U7") (pin "6") (pinfunction "COL_6") (pintype "unspecified"))
    )
    (net (code "45") (name "/SENSE_DRV") (class "Default")
      (node (ref "RSH2") (pin "3") (pinfunction "SENSE_DRV_3") (pintype "unspecified"))
      (node (ref "TP3") (pin "1") (pinfunction "TP_1") (pintype "unspecified"))
      (node (ref "U3") (pin "2") (pinfunction "IN-_2") (pintype "unspecified"))
    )
    (net (code "46") (name "/SENSE_SPK") (class "Default")
      (node (ref "RSH2") (pin "4") (pinfunction "SENSE_SPK_4") (pintype "unspecified"))
      (node (ref "TP4") (pin "1") (pinfunction "TP_1") (pintype "unspecified"))
      (node (ref "U3") (pin "3") (pinfunction "IN+_3") (pintype "unspecified"))
    )
    (net (code "47") (name "/SERVO_INT_N") (class "Default")
      (node (ref "C30") (pin "2") (pinfunction "2_2") (pintype "unspecified"))
      (node (ref "R40") (pin "2") (pinfunction "2_2") (pintype "unspecified"))
      (node (ref "R41") (pin "2") (pinfunction "2_2") (pintype "unspecified"))
      (node (ref "R42") (pin "2") (pinfunction "2_2") (pintype "unspecified"))
      (node (ref "U10") (pin "2") (pinfunction "S1_2") (pintype "unspecified"))
      (node (ref "U9") (pin "2") (pinfunction "-INA_2") (pintype "unspecified"))
    )
    (net (code "48") (name "/SNUB_MID") (class "Default")
      (node (ref "C4") (pin "1") (pinfunction "1_1") (pintype "unspecified"))
      (node (ref "R12") (pin "2") (pinfunction "2_2") (pintype "unspecified"))
    )
    (net (code "49") (name "/SPI_MISO") (class "Default")
      (node (ref "J10") (pin "3") (pinfunction "3_3") (pintype "unspecified"))
      (node (ref "U5") (pin "41") (pinfunction "PB4_41") (pintype "unspecified"))
    )
    (net (code "50") (name "/SPI_MOSI") (class "Default")
      (node (ref "J10") (pin "4") (pinfunction "4_4") (pintype "unspecified"))
      (node (ref "U5") (pin "42") (pinfunction "PB5_42") (pintype "unspecified"))
    )
    (net (code "51") (name "/SPI_NSS") (class "Default")
      (node (ref "J10") (pin "1") (pinfunction "1_1") (pintype "unspecified"))
      (node (ref "U5") (pin "39") (pinfunction "PA15_39") (pintype "unspecified"))
    )
    (net (code "52") (name "/SPI_SCK") (class "Default")
      (node (ref "J10") (pin "2") (pinfunction "2_2") (pintype "unspecified"))
      (node (ref "U5") (pin "40") (pinfunction "PB3_40") (pintype "unspecified"))
    )
    (net (code "53") (name "/SPK") (class "Default")
      (node (ref "D3") (pin "2") (pinfunction "A_2") (pintype "unspecified"))
      (node (ref "D4") (pin "1") (pinfunction "K_1") (pintype "unspecified"))
      (node (ref "J4") (pin "1") (pinfunction "1_1") (pintype "unspecified"))
      (node (ref "R25") (pin "1") (pinfunction "1_1") (pintype "unspecified"))
      (node (ref "R6") (pin "1") (pinfunction "1_1") (pintype "input"))
      (node (ref "RSH2") (pin "2") (pinfunction "FORCE_SPK_2") (pintype "unspecified"))
      (node (ref "TP1") (pin "1") (pinfunction "TP_1") (pintype "unspecified"))
    )
    (net (code "54") (name "/SWCLK") (class "Default")
      (node (ref "J7") (pin "3") (pinfunction "3_3") (pintype "unspecified"))
      (node (ref "U5") (pin "38") (pinfunction "PA14_38") (pintype "unspecified"))
    )
    (net (code "55") (name "/SWDIO") (class "Default")
      (node (ref "J7") (pin "2") (pinfunction "2_2") (pintype "unspecified"))
      (node (ref "U5") (pin "37") (pinfunction "PA13_37") (pintype "unspecified"))
    )
    (net (code "56") (name "/TIM_SYNC") (class "Default")
      (node (ref "J10") (pin "5") (pinfunction "5_5") (pintype "unspecified"))
      (node (ref "U5") (pin "30") (pinfunction "PA8_30") (pintype "unspecified"))
    )
    (net (code "57") (name "/U4A_LEAD_MID") (class "Default")
      (node (ref "C36") (pin "1") (pinfunction "1_1") (pintype "unspecified"))
      (node (ref "R44") (pin "2") (pinfunction "2_2") (pintype "unspecified"))
    )
    (net (code "58") (name "/U4A_N") (class "Default")
      (node (ref "C13") (pin "2") (pinfunction "2_2") (pintype "unspecified"))
      (node (ref "C31") (pin "2") (pinfunction "2_2") (pintype "unspecified"))
      (node (ref "C32") (pin "2") (pinfunction "2_2") (pintype "unspecified"))
      (node (ref "C33") (pin "2") (pinfunction "2_2") (pintype "unspecified"))
      (node (ref "C34") (pin "2") (pinfunction "2_2") (pintype "unspecified"))
      (node (ref "C35") (pin "2") (pinfunction "2_2") (pintype "unspecified"))
      (node (ref "C36") (pin "2") (pinfunction "2_2") (pintype "unspecified"))
      (node (ref "R13") (pin "1") (pinfunction "1_1") (pintype "unspecified"))
      (node (ref "R14") (pin "2") (pinfunction "2_2") (pintype "unspecified"))
      (node (ref "R34") (pin "2") (pinfunction "2_2") (pintype "unspecified"))
      (node (ref "U4") (pin "2") (pinfunction "-INA_2") (pintype "unspecified"))
    )
    (net (code "59") (name "/U4B_LEAD_MID") (class "Default")
      (node (ref "C42") (pin "1") (pinfunction "1_1") (pintype "unspecified"))
      (node (ref "R45") (pin "2") (pinfunction "2_2") (pintype "unspecified"))
    )
    (net (code "60") (name "/U4B_N") (class "Default")
      (node (ref "C14") (pin "2") (pinfunction "2_2") (pintype "unspecified"))
      (node (ref "C37") (pin "2") (pinfunction "2_2") (pintype "unspecified"))
      (node (ref "C38") (pin "2") (pinfunction "2_2") (pintype "unspecified"))
      (node (ref "C39") (pin "2") (pinfunction "2_2") (pintype "unspecified"))
      (node (ref "C40") (pin "2") (pinfunction "2_2") (pintype "unspecified"))
      (node (ref "C41") (pin "2") (pinfunction "2_2") (pintype "unspecified"))
      (node (ref "C42") (pin "2") (pinfunction "2_2") (pintype "unspecified"))
      (node (ref "R15") (pin "1") (pinfunction "1_1") (pintype "unspecified"))
      (node (ref "R16") (pin "2") (pinfunction "2_2") (pintype "unspecified"))
      (node (ref "U4") (pin "6") (pinfunction "-INB_6") (pintype "unspecified"))
    )
    (net (code "61") (name "/UART_RX") (class "Default")
      (node (ref "J8") (pin "2") (pinfunction "2_2") (pintype "unspecified"))
      (node (ref "U5") (pin "32") (pinfunction "PA10_32") (pintype "unspecified"))
    )
    (net (code "62") (name "/UART_TX") (class "Default")
      (node (ref "J8") (pin "1") (pinfunction "1_1") (pintype "unspecified"))
      (node (ref "U5") (pin "31") (pinfunction "PA9_31") (pintype "unspecified"))
    )
    (net (code "63") (name "/V3V3") (class "Default")
      (node (ref "C19") (pin "1") (pinfunction "1_1") (pintype "unspecified"))
      (node (ref "C2") (pin "1") (pinfunction "1_1") (pintype "unspecified"))
      (node (ref "C20") (pin "1") (pinfunction "1_1") (pintype "unspecified"))
      (node (ref "C21") (pin "1") (pinfunction "1_1") (pintype "unspecified"))
      (node (ref "C24") (pin "1") (pinfunction "1_1") (pintype "unspecified"))
      (node (ref "C3") (pin "1") (pinfunction "1_1") (pintype "unspecified"))
      (node (ref "FB3") (pin "1") (pinfunction "1_1") (pintype "unspecified"))
      (node (ref "J11") (pin "1") (pinfunction "1_1") (pintype "unspecified"))
      (node (ref "J7") (pin "1") (pinfunction "1_1") (pintype "unspecified"))
      (node (ref "R23") (pin "1") (pinfunction "1_1") (pintype "unspecified"))
      (node (ref "R24") (pin "2") (pinfunction "2_2") (pintype "unspecified"))
      (node (ref "R32") (pin "2") (pinfunction "2_2") (pintype "unspecified"))
      (node (ref "R33") (pin "2") (pinfunction "2_2") (pintype "unspecified"))
      (node (ref "TP15") (pin "1") (pinfunction "TP_1") (pintype "unspecified"))
      (node (ref "U5") (pin "1") (pinfunction "VBAT_1") (pintype "unspecified"))
      (node (ref "U5") (pin "24") (pinfunction "VDD_24") (pintype "unspecified"))
      (node (ref "U5") (pin "36") (pinfunction "VDD_36") (pintype "unspecified"))
      (node (ref "U5") (pin "48") (pinfunction "VDD_48") (pintype "unspecified"))
      (node (ref "U6") (pin "2") (pinfunction "VOUT_2") (pintype "unspecified"))
      (node (ref "U6") (pin "4") (pinfunction "VOUT_4") (pintype "unspecified"))
    )
    (net (code "64") (name "/V3V3A") (class "Default")
      (node (ref "C22") (pin "1") (pinfunction "1_1") (pintype "unspecified"))
      (node (ref "C23") (pin "1") (pinfunction "1_1") (pintype "unspecified"))
      (node (ref "C25") (pin "1") (pinfunction "1_1") (pintype "unspecified"))
      (node (ref "FB3") (pin "2") (pinfunction "2_2") (pintype "unspecified"))
      (node (ref "R19") (pin "1") (pinfunction "1_1") (pintype "unspecified"))
      (node (ref "U5") (pin "20") (pinfunction "VREF+_20") (pintype "unspecified"))
      (node (ref "U5") (pin "21") (pinfunction "VDDA_21") (pintype "unspecified"))
    )
    (net (code "65") (name "/V5_IN") (class "Default")
      (node (ref "C1") (pin "1") (pinfunction "1_1") (pintype "unspecified"))
      (node (ref "J3") (pin "1") (pinfunction "1_1") (pintype "unspecified"))
      (node (ref "U6") (pin "3") (pinfunction "VIN_3") (pintype "unspecified"))
    )
    (net (code "66") (name "/VCMD") (class "Default")
      (node (ref "C14") (pin "1") (pinfunction "1_1") (pintype "unspecified"))
      (node (ref "C37") (pin "1") (pinfunction "1_1") (pintype "unspecified"))
      (node (ref "C38") (pin "1") (pinfunction "1_1") (pintype "unspecified"))
      (node (ref "C39") (pin "1") (pinfunction "1_1") (pintype "unspecified"))
      (node (ref "C40") (pin "1") (pinfunction "1_1") (pintype "unspecified"))
      (node (ref "C41") (pin "1") (pinfunction "1_1") (pintype "unspecified"))
      (node (ref "R16") (pin "1") (pinfunction "1_1") (pintype "unspecified"))
      (node (ref "R45") (pin "1") (pinfunction "1_1") (pintype "unspecified"))
      (node (ref "R5") (pin "1") (pinfunction "1_1") (pintype "unspecified"))
      (node (ref "TP8") (pin "1") (pinfunction "TP_1") (pintype "unspecified"))
      (node (ref "U4") (pin "7") (pinfunction "OUTB_7") (pintype "unspecified"))
    )
    (net (code "67") (name "/VK") (class "Default")
      (node (ref "J5") (pin "2") (pinfunction "2_2") (pintype "unspecified"))
      (node (ref "TP6") (pin "1") (pinfunction "TP_1") (pintype "unspecified"))
      (node (ref "U2") (pin "1") (pinfunction "Y1_1") (pintype "unspecified"))
    )
    (net (code "68") (name "/VK_AMP_N") (class "Default")
      (node (ref "R21") (pin "1") (pinfunction "1_1") (pintype "unspecified"))
      (node (ref "R22") (pin "2") (pinfunction "2_2") (pintype "unspecified"))
      (node (ref "U8") (pin "6") (pinfunction "-INB_6") (pintype "unspecified"))
    )
    (net (code "69") (name "/VK_EXT") (class "Default")
      (node (ref "J5") (pin "3") (pinfunction "3_3") (pintype "unspecified"))
      (node (ref "J6") (pin "1") (pinfunction "1_1") (pintype "unspecified"))
    )
    (net (code "70") (name "/VK_MCU") (class "Default")
      (node (ref "J5") (pin "1") (pinfunction "1_1") (pintype "unspecified"))
      (node (ref "R22") (pin "1") (pinfunction "1_1") (pintype "unspecified"))
      (node (ref "U8") (pin "7") (pinfunction "OUTB_7") (pintype "unspecified"))
    )
    (net (code "71") (name "/VREF_0V477") (class "Default")
      (node (ref "C18") (pin "1") (pinfunction "1_1") (pintype "unspecified"))
      (node (ref "R19") (pin "2") (pinfunction "2_2") (pintype "unspecified"))
      (node (ref "R20") (pin "1") (pinfunction "1_1") (pintype "unspecified"))
      (node (ref "R21") (pin "2") (pinfunction "2_2") (pintype "unspecified"))
    )
    (net (code "72") (name "/VSENSE_RAW") (class "Default")
      (node (ref "TP18") (pin "1") (pinfunction "TP_1") (pintype "unspecified"))
      (node (ref "U3") (pin "6") (pinfunction "VOUT_6") (pintype "output"))
      (node (ref "U4") (pin "3") (pinfunction "+INA_3") (pintype "unspecified"))
    )
    (net (code "73") (name "/ZSERVO_OUT") (class "Default")
      (node (ref "C30") (pin "1") (pinfunction "1_1") (pintype "unspecified"))
      (node (ref "R38") (pin "1") (pinfunction "1_1") (pintype "unspecified"))
      (node (ref "R41") (pin "1") (pinfunction "1_1") (pintype "unspecified"))
      (node (ref "R42") (pin "1") (pinfunction "1_1") (pintype "unspecified"))
      (node (ref "R43") (pin "1") (pinfunction "1_1") (pintype "unspecified"))
      (node (ref "U10") (pin "1") (pinfunction "D_1") (pintype "unspecified"))
      (node (ref "U9") (pin "1") (pinfunction "OUTA_1") (pintype "unspecified"))
    )
    (net (code "74") (name "/ZTRIM") (class "Default")
      (node (ref "J14") (pin "1") (pinfunction "1_1") (pintype "unspecified"))
      (node (ref "J14") (pin "2") (pinfunction "2_2") (pintype "unspecified"))
      (node (ref "R37") (pin "1") (pinfunction "1_1") (pintype "unspecified"))
    )
    (net (code "75") (name "Net-(U9--INB)") (class "Default")
      (node (ref "U9") (pin "6") (pinfunction "-INB_6") (pintype "unspecified"))
      (node (ref "U9") (pin "7") (pinfunction "OUTB_7") (pintype "unspecified"))
    )
    (net (code "76") (name "Net-(U10-EN)") (class "Default")
      (node (ref "R23") (pin "2") (pinfunction "2_2") (pintype "unspecified"))
      (node (ref "TP_SERVO_RST") (pin "1") (pinfunction "1_1") (pintype "input"))
      (node (ref "U10") (pin "5") (pinfunction "EN_5") (pintype "unspecified"))
    )
    (net (code "77") (name "unconnected-(U3-NC-Pad8)") (class "Default")
      (node (ref "U3") (pin "8") (pinfunction "NC_8") (pintype "unspecified+no_connect"))
    )
    (net (code "78") (name "unconnected-(U5-PA11-Pad33)") (class "Default")
      (node (ref "U5") (pin "33") (pinfunction "PA11_33") (pintype "unspecified+no_connect"))
    )
    (net (code "79") (name "unconnected-(U5-PA12-Pad34)") (class "Default")
      (node (ref "U5") (pin "34") (pinfunction "PA12_34") (pintype "unspecified+no_connect"))
    )
    (net (code "80") (name "unconnected-(U5-PB2-Pad18)") (class "Default")
      (node (ref "U5") (pin "18") (pinfunction "PB2_18") (pintype "unspecified+no_connect"))
    )
    (net (code "81") (name "unconnected-(U5-PB6-Pad43)") (class "Default")
      (node (ref "U5") (pin "43") (pinfunction "PB6_43") (pintype "unspecified+no_connect"))
    )
    (net (code "82") (name "unconnected-(U5-PC13-Pad2)") (class "Default")
      (node (ref "U5") (pin "2") (pinfunction "PC13_2") (pintype "unspecified+no_connect"))
    )
    (net (code "83") (name "unconnected-(U5-PC14-OSC32_IN-Pad3)") (class "Default")
      (node (ref "U5") (pin "3") (pinfunction "PC14-OSC32_IN_3") (pintype "unspecified+no_connect"))
    )
    (net (code "84") (name "unconnected-(U5-PC15-OSC32_OUT-Pad4)") (class "Default")
      (node (ref "U5") (pin "4") (pinfunction "PC15-OSC32_OUT_4") (pintype "unspecified+no_connect"))
    )
    (net (code "85") (name "unconnected-(U5-PF0-OSC_IN-Pad5)") (class "Default")
      (node (ref "U5") (pin "5") (pinfunction "PF0-OSC_IN_5") (pintype "unspecified+no_connect"))
    )
    (net (code "86") (name "unconnected-(U5-PF1-OSC_OUT-Pad6)") (class "Default")
      (node (ref "U5") (pin "6") (pinfunction "PF1-OSC_OUT_6") (pintype "unspecified+no_connect"))
    )
  )
)
